# Power.net
KiCad netlist of a schematic drawn in Altium Designer
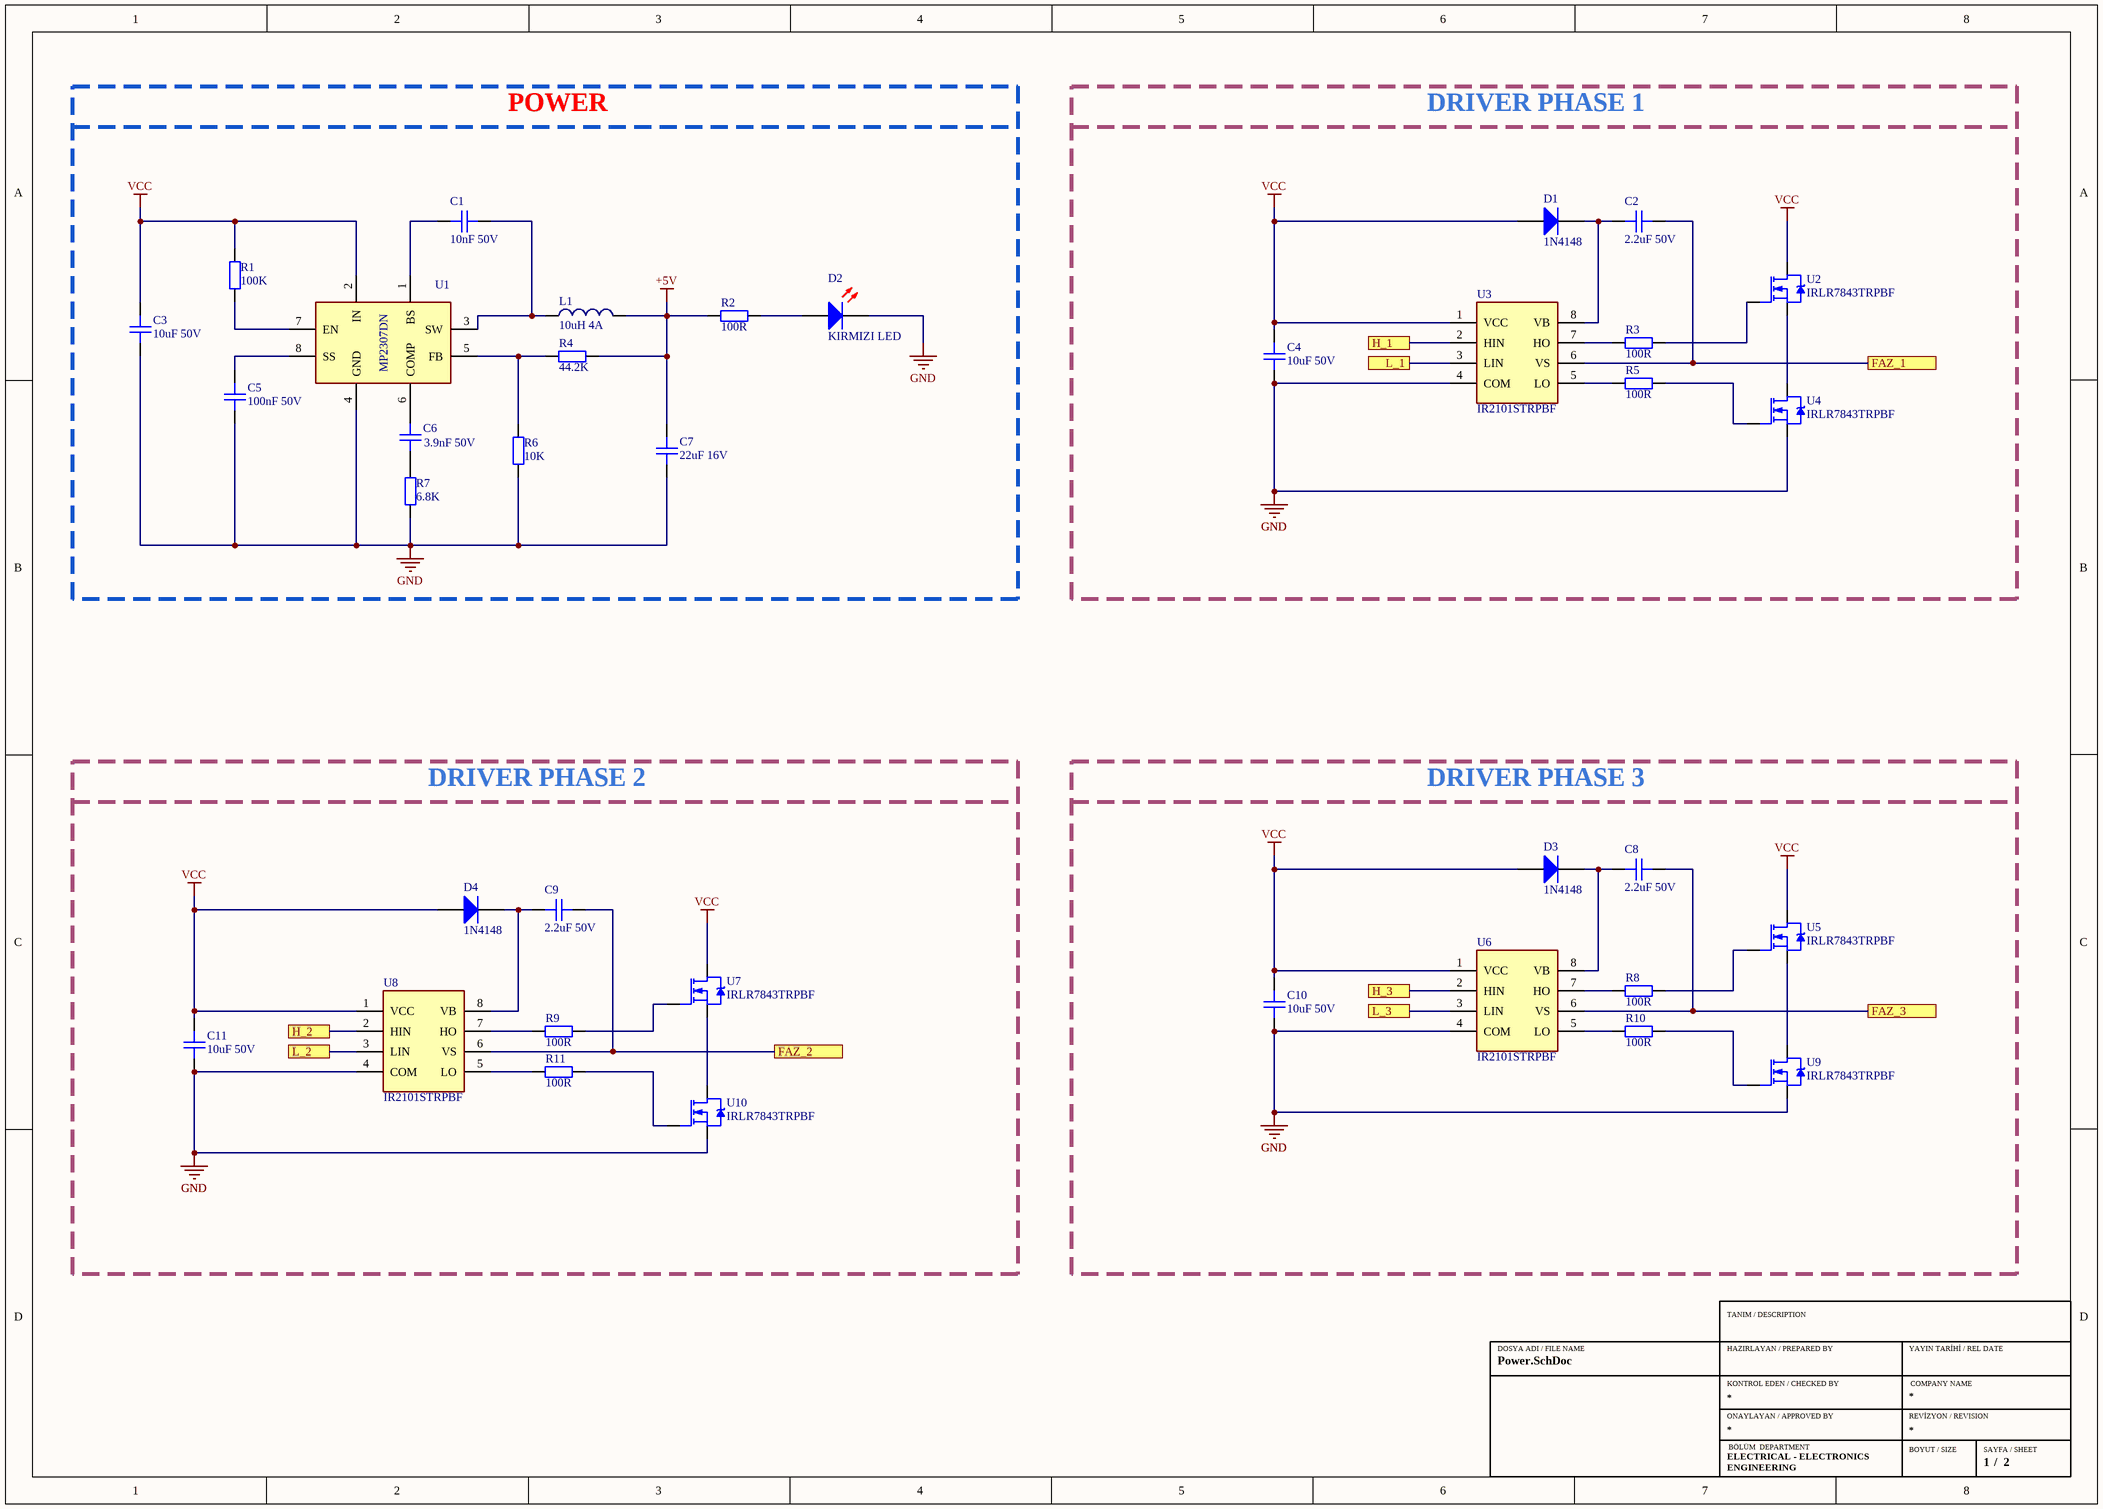
[diagram p0: Power.SchDoc]

(export (version "E")
  (design (tool "Eeschema 10.0.6"))
  (components
    (comp (ref "C1")
      (value "CAP CER 10000PF 50V X7R 0805")
      (footprint "CAP 0805/2012")
      (description "10000pF ±10% 50V Ceramic Capacitor X7R 0805 (2012 Metric)")
      (fields (field (name "DEGER") "10nF 50V"))
      (libsource (lib "PROJE") (part "10nF 50V 0805"))
    )
    (comp (ref "C2")
      (value "CAP CER 2.2UF 50V X5R 1206")
      (footprint "CAP 1206/3216")
      (description "2.2µF ±10% 50V Ceramic Capacitor X5R 1206 (3216 Metric)")
      (fields (field (name "DEGER") "2.2uF 50V"))
      (libsource (lib "PROJE") (part "2.2uF 50V 1206"))
    )
    (comp (ref "C3")
      (value "CAP CER 10UF 50V X5R 1206")
      (footprint "CAP 1206/3216")
      (description "10µF ±10% 50V Ceramic Capacitor X5R 1206 (3216 Metric)")
      (fields (field (name "DEGER") "10uF 50V"))
      (libsource (lib "PROJE") (part "10uF 50V 1206"))
    )
    (comp (ref "C4")
      (value "CAP CER 10UF 50V X5R 1206")
      (footprint "CAP 1206/3216")
      (description "10µF ±10% 50V Ceramic Capacitor X5R 1206 (3216 Metric)")
      (fields (field (name "DEGER") "10uF 50V"))
      (libsource (lib "PROJE") (part "10uF 50V 1206"))
    )
    (comp (ref "C5")
      (value "CAP CER 0.1UF 50V X7R 0805")
      (footprint "CAP 0805/2012")
      (description "0.1µF ±10% 50V Ceramic Capacitor X7R 0805 (2012 Metric)")
      (fields (field (name "DEGER") "100nF 50V"))
      (libsource (lib "PROJE") (part "100nF 50V 0805"))
    )
    (comp (ref "C6")
      (value "CAP CER 3900PF 50V X7R 0805")
      (footprint "CAP 0805/2012")
      (description "3900pF ±10% 50V Ceramic Capacitor X7R 0805 (2012 Metric)")
      (fields (field (name "DEGER") "3.9nF 50V"))
      (libsource (lib "PROJE") (part "3.9nF 50V 0805"))
    )
    (comp (ref "C7")
      (value "CAP CERAMIC 22UF 16V X7S 20% PAD")
      (footprint "CAP 1206/3216")
      (description "22µF ±20% 16V Ceramic Capacitor X7S 1206 (3216 Metric)")
      (fields (field (name "DEGER") "22uF 16V"))
      (libsource (lib "PROJE") (part "22uF 16V 1206"))
    )
    (comp (ref "C8")
      (value "CAP CER 2.2UF 50V X5R 1206")
      (footprint "CAP 1206/3216")
      (description "2.2µF ±10% 50V Ceramic Capacitor X5R 1206 (3216 Metric)")
      (fields (field (name "DEGER") "2.2uF 50V"))
      (libsource (lib "PROJE") (part "2.2uF 50V 1206"))
    )
    (comp (ref "C9")
      (value "CAP CER 2.2UF 50V X5R 1206")
      (footprint "CAP 1206/3216")
      (description "2.2µF ±10% 50V Ceramic Capacitor X5R 1206 (3216 Metric)")
      (fields (field (name "DEGER") "2.2uF 50V"))
      (libsource (lib "PROJE") (part "2.2uF 50V 1206"))
    )
    (comp (ref "C10")
      (value "CAP CER 10UF 50V X5R 1206")
      (footprint "CAP 1206/3216")
      (description "10µF ±10% 50V Ceramic Capacitor X5R 1206 (3216 Metric)")
      (fields (field (name "DEGER") "10uF 50V"))
      (libsource (lib "PROJE") (part "10uF 50V 1206"))
    )
    (comp (ref "C11")
      (value "CAP CER 10UF 50V X5R 1206")
      (footprint "CAP 1206/3216")
      (description "10µF ±10% 50V Ceramic Capacitor X5R 1206 (3216 Metric)")
      (fields (field (name "DEGER") "10uF 50V"))
      (libsource (lib "PROJE") (part "10uF 50V 1206"))
    )
    (comp (ref "D1")
      (value "1N4148 Diyot")
      (footprint "SOD-123")
      (description "DIODE GEN PURP 100V 150MA SOD123")
      (fields (field (name "DEGER") "1N4148"))
      (libsource (lib "PROJE") (part "1N4148"))
    )
    (comp (ref "D2")
      (value "Red 645nm LED Indication - Discrete 1.8V 0805")
      (footprint "SMD: LED 0805/2012 RED")
      (description "LED RED DIFFUSED 0805 SMD")
      (fields (field (name "DEGER") "KIRMIZI LED"))
      (libsource (lib "PROJE") (part "LED_Kırmızı"))
    )
    (comp (ref "D3")
      (value "1N4148 Diyot")
      (footprint "SOD-123")
      (description "DIODE GEN PURP 100V 150MA SOD123")
      (fields (field (name "DEGER") "1N4148"))
      (libsource (lib "PROJE") (part "1N4148"))
    )
    (comp (ref "D4")
      (value "1N4148 Diyot")
      (footprint "SOD-123")
      (description "DIODE GEN PURP 100V 150MA SOD123")
      (fields (field (name "DEGER") "1N4148"))
      (libsource (lib "PROJE") (part "1N4148"))
    )
    (comp (ref "L1")
      (value "FIXED IND 10UH 4A 68 MOHM SMD")
      (footprint "ASPI-0630LR-100M-T15")
      (description "10µH Shielded Molded Inductor 4A 68mOhm Max Nonstandard")
      (fields (field (name "DEGER") "10uH 4A"))
      (libsource (lib "PROJE") (part "10uH 4A"))
    )
    (comp (ref "R1")
      (value "RES SMD 100K OHM 1% 1/8W 0805")
      (footprint "RES_0805")
      (description "100 kOhms ±1% 0.125W, 1/8W Chip Resistor 0805 (2012 Metric) Moisture Resistant Thick Film")
      (fields (field (name "DEGER") "100K"))
      (libsource (lib "PROJE") (part "100K 0805"))
    )
    (comp (ref "R2")
      (value "RES SMD 100 OHM 1% 1/8W 0805")
      (footprint "RES_0805")
      (description "100 Ohms ±1% 0.125W, 1/8W Chip Resistor 0805 (2012 Metric) Moisture Resistant Thick Film")
      (fields (field (name "DEGER") "100R"))
      (libsource (lib "PROJE") (part "100R 0805"))
    )
    (comp (ref "R3")
      (value "RES SMD 100 OHM 1% 1/8W 0805")
      (footprint "RES_0805")
      (description "100 Ohms ±1% 0.125W, 1/8W Chip Resistor 0805 (2012 Metric) Moisture Resistant Thick Film")
      (fields (field (name "DEGER") "100R"))
      (libsource (lib "PROJE") (part "100R 0805"))
    )
    (comp (ref "R4")
      (value "RES SMD 44.2K OHM 1% 1/8W 0805")
      (footprint "RES_0805")
      (description "44.2 kOhms ±1% 0.125W, 1/8W Chip Resistor 0805 (2012 Metric) Moisture Resistant Thick Film")
      (fields (field (name "DEGER") "44.2K"))
      (libsource (lib "PROJE") (part "44.2K 0805"))
    )
    (comp (ref "R5")
      (value "RES SMD 100 OHM 1% 1/8W 0805")
      (footprint "RES_0805")
      (description "100 Ohms ±1% 0.125W, 1/8W Chip Resistor 0805 (2012 Metric) Moisture Resistant Thick Film")
      (fields (field (name "DEGER") "100R"))
      (libsource (lib "PROJE") (part "100R 0805"))
    )
    (comp (ref "R6")
      (value "RES SMD 10K OHM 1% 1/8W 0805")
      (footprint "RES_0805")
      (description "10 kOhms ±1% 0.125W, 1/8W Chip Resistor 0805 (2012 Metric) Moisture Resistant Thick Film")
      (fields (field (name "DEGER") "10K"))
      (libsource (lib "PROJE") (part "10K 0805"))
    )
    (comp (ref "R7")
      (value "RES SMD 6.8K OHM 1% 1/8W 0805")
      (footprint "RES_0805")
      (description "6.8 kOhms ±1% 0.125W, 1/8W Chip Resistor 0805 (2012 Metric) Moisture Resistant Thick Film")
      (fields (field (name "DEGER") "6.8K"))
      (libsource (lib "PROJE") (part "6.8K 0805"))
    )
    (comp (ref "R8")
      (value "RES SMD 100 OHM 1% 1/8W 0805")
      (footprint "RES_0805")
      (description "100 Ohms ±1% 0.125W, 1/8W Chip Resistor 0805 (2012 Metric) Moisture Resistant Thick Film")
      (fields (field (name "DEGER") "100R"))
      (libsource (lib "PROJE") (part "100R 0805"))
    )
    (comp (ref "R9")
      (value "RES SMD 100 OHM 1% 1/8W 0805")
      (footprint "RES_0805")
      (description "100 Ohms ±1% 0.125W, 1/8W Chip Resistor 0805 (2012 Metric) Moisture Resistant Thick Film")
      (fields (field (name "DEGER") "100R"))
      (libsource (lib "PROJE") (part "100R 0805"))
    )
    (comp (ref "R10")
      (value "RES SMD 100 OHM 1% 1/8W 0805")
      (footprint "RES_0805")
      (description "100 Ohms ±1% 0.125W, 1/8W Chip Resistor 0805 (2012 Metric) Moisture Resistant Thick Film")
      (fields (field (name "DEGER") "100R"))
      (libsource (lib "PROJE") (part "100R 0805"))
    )
    (comp (ref "R11")
      (value "RES SMD 100 OHM 1% 1/8W 0805")
      (footprint "RES_0805")
      (description "100 Ohms ±1% 0.125W, 1/8W Chip Resistor 0805 (2012 Metric) Moisture Resistant Thick Film")
      (fields (field (name "DEGER") "100R"))
      (libsource (lib "PROJE") (part "100R 0805"))
    )
    (comp (ref "U1")
      (value "IC REG BUCK ADJUSTABLE 3A 8SOIC")
      (footprint "SOIC8_PAD")
      (fields (field (name "DEGER") "MP2307DN"))
      (libsource (lib "PROJE") (part "MP2307DN"))
    )
    (comp (ref "U2")
      (value "MOSFET N-CH 30V 161A DPAK")
      (footprint "DPAK")
      (description "N-Channel 30V 161A (Tc) 140W (Tc) Surface Mount D-Pak")
      (fields (field (name "DEGER") "IRLR7843TRPBF"))
      (libsource (lib "PROJE") (part "IRLR7843"))
    )
    (comp (ref "U3")
      (value "IC GATE DRVR HALF-BRIDGE 8SOIC")
      (footprint "SOIC8")
      (description "Half-Bridge Gate Driver IC Non-Inverting 8-SOIC")
      (fields (field (name "DEGER") "IR2101STRPBF"))
      (libsource (lib "PROJE") (part "IR2101"))
    )
    (comp (ref "U4")
      (value "MOSFET N-CH 30V 161A DPAK")
      (footprint "DPAK")
      (description "N-Channel 30V 161A (Tc) 140W (Tc) Surface Mount D-Pak")
      (fields (field (name "DEGER") "IRLR7843TRPBF"))
      (libsource (lib "PROJE") (part "IRLR7843"))
    )
    (comp (ref "U5")
      (value "MOSFET N-CH 30V 161A DPAK")
      (footprint "DPAK")
      (description "N-Channel 30V 161A (Tc) 140W (Tc) Surface Mount D-Pak")
      (fields (field (name "DEGER") "IRLR7843TRPBF"))
      (libsource (lib "PROJE") (part "IRLR7843"))
    )
    (comp (ref "U6")
      (value "IC GATE DRVR HALF-BRIDGE 8SOIC")
      (footprint "SOIC8")
      (description "Half-Bridge Gate Driver IC Non-Inverting 8-SOIC")
      (fields (field (name "DEGER") "IR2101STRPBF"))
      (libsource (lib "PROJE") (part "IR2101"))
    )
    (comp (ref "U7")
      (value "MOSFET N-CH 30V 161A DPAK")
      (footprint "DPAK")
      (description "N-Channel 30V 161A (Tc) 140W (Tc) Surface Mount D-Pak")
      (fields (field (name "DEGER") "IRLR7843TRPBF"))
      (libsource (lib "PROJE") (part "IRLR7843"))
    )
    (comp (ref "U8")
      (value "IC GATE DRVR HALF-BRIDGE 8SOIC")
      (footprint "SOIC8")
      (description "Half-Bridge Gate Driver IC Non-Inverting 8-SOIC")
      (fields (field (name "DEGER") "IR2101STRPBF"))
      (libsource (lib "PROJE") (part "IR2101"))
    )
    (comp (ref "U9")
      (value "MOSFET N-CH 30V 161A DPAK")
      (footprint "DPAK")
      (description "N-Channel 30V 161A (Tc) 140W (Tc) Surface Mount D-Pak")
      (fields (field (name "DEGER") "IRLR7843TRPBF"))
      (libsource (lib "PROJE") (part "IRLR7843"))
    )
    (comp (ref "U10")
      (value "MOSFET N-CH 30V 161A DPAK")
      (footprint "DPAK")
      (description "N-Channel 30V 161A (Tc) 140W (Tc) Surface Mount D-Pak")
      (fields (field (name "DEGER") "IRLR7843TRPBF"))
      (libsource (lib "PROJE") (part "IRLR7843"))
    )
  )
  (nets
    (net (code "1") (name "+5V") (class "Default")
      (node (ref "C7") (pin "2") (pinfunction "2_2") (pintype "passive"))
      (node (ref "L1") (pin "2") (pinfunction "2_2") (pintype "passive"))
      (node (ref "R2") (pin "1") (pinfunction "1_1") (pintype "passive"))
      (node (ref "R4") (pin "2") (pinfunction "2_2") (pintype "passive"))
    )
    (net (code "2") (name "/FAZ_1") (class "Default")
      (node (ref "C2") (pin "2") (pinfunction "2_2") (pintype "passive"))
      (node (ref "U3") (pin "6") (pinfunction "VS_6") (pintype "passive"))
    )
    (net (code "3") (name "/FAZ_2") (class "Default")
      (node (ref "C9") (pin "2") (pinfunction "2_2") (pintype "passive"))
      (node (ref "U8") (pin "6") (pinfunction "VS_6") (pintype "passive"))
    )
    (net (code "4") (name "/FAZ_3") (class "Default")
      (node (ref "C8") (pin "2") (pinfunction "2_2") (pintype "passive"))
      (node (ref "U6") (pin "6") (pinfunction "VS_6") (pintype "passive"))
    )
    (net (code "5") (name "/H_1") (class "Default")
      (node (ref "U3") (pin "2") (pinfunction "HIN_2") (pintype "passive"))
    )
    (net (code "6") (name "/H_2") (class "Default")
      (node (ref "U8") (pin "2") (pinfunction "HIN_2") (pintype "passive"))
    )
    (net (code "7") (name "/H_3") (class "Default")
      (node (ref "U6") (pin "2") (pinfunction "HIN_2") (pintype "passive"))
    )
    (net (code "8") (name "/L_1") (class "Default")
      (node (ref "U3") (pin "3") (pinfunction "LIN_3") (pintype "passive"))
    )
    (net (code "9") (name "/L_2") (class "Default")
      (node (ref "U8") (pin "3") (pinfunction "LIN_3") (pintype "passive"))
    )
    (net (code "10") (name "/L_3") (class "Default")
      (node (ref "U6") (pin "3") (pinfunction "LIN_3") (pintype "passive"))
    )
    (net (code "11") (name "GND") (class "Default")
      (node (ref "C10") (pin "1") (pinfunction "1_1") (pintype "passive"))
      (node (ref "C11") (pin "1") (pinfunction "1_1") (pintype "passive"))
      (node (ref "C3") (pin "1") (pinfunction "1_1") (pintype "passive"))
      (node (ref "C4") (pin "1") (pinfunction "1_1") (pintype "passive"))
      (node (ref "C5") (pin "1") (pinfunction "1_1") (pintype "passive"))
      (node (ref "C7") (pin "1") (pinfunction "1_1") (pintype "passive"))
      (node (ref "D2") (pin "2") (pinfunction "K_2") (pintype "passive"))
      (node (ref "R6") (pin "1") (pinfunction "1_1") (pintype "passive"))
      (node (ref "R7") (pin "1") (pinfunction "1_1") (pintype "passive"))
      (node (ref "U1") (pin "4") (pinfunction "GND_4") (pintype "passive"))
      (node (ref "U10") (pin "3") (pinfunction "S_3") (pintype "passive"))
      (node (ref "U3") (pin "4") (pinfunction "COM_4") (pintype "passive"))
      (node (ref "U4") (pin "3") (pinfunction "S_3") (pintype "passive"))
      (node (ref "U6") (pin "4") (pinfunction "COM_4") (pintype "passive"))
      (node (ref "U8") (pin "4") (pinfunction "COM_4") (pintype "passive"))
      (node (ref "U9") (pin "3") (pinfunction "S_3") (pintype "passive"))
    )
    (net (code "12") (name "Net-(C6-Pad1)") (class "Default")
      (node (ref "C6") (pin "1") (pinfunction "1_1") (pintype "passive"))
      (node (ref "R7") (pin "2") (pinfunction "2_2") (pintype "passive"))
    )
    (net (code "13") (name "Net-(D1-K)") (class "Default")
      (node (ref "C2") (pin "1") (pinfunction "1_1") (pintype "passive"))
      (node (ref "D1") (pin "2") (pinfunction "K_2") (pintype "passive"))
      (node (ref "U3") (pin "8") (pinfunction "VB_8") (pintype "passive"))
    )
    (net (code "14") (name "Net-(D2-A)") (class "Default")
      (node (ref "D2") (pin "1") (pinfunction "A_1") (pintype "passive"))
      (node (ref "R2") (pin "2") (pinfunction "2_2") (pintype "passive"))
    )
    (net (code "15") (name "Net-(D3-K)") (class "Default")
      (node (ref "C8") (pin "1") (pinfunction "1_1") (pintype "passive"))
      (node (ref "D3") (pin "2") (pinfunction "K_2") (pintype "passive"))
      (node (ref "U6") (pin "8") (pinfunction "VB_8") (pintype "passive"))
    )
    (net (code "16") (name "Net-(D4-K)") (class "Default")
      (node (ref "C9") (pin "1") (pinfunction "1_1") (pintype "passive"))
      (node (ref "D4") (pin "2") (pinfunction "K_2") (pintype "passive"))
      (node (ref "U8") (pin "8") (pinfunction "VB_8") (pintype "passive"))
    )
    (net (code "17") (name "Net-(U1-BS)") (class "Default")
      (node (ref "C1") (pin "1") (pinfunction "1_1") (pintype "passive"))
      (node (ref "U1") (pin "1") (pinfunction "BS_1") (pintype "passive"))
    )
    (net (code "18") (name "Net-(U1-COMP)") (class "Default")
      (node (ref "C6") (pin "2") (pinfunction "2_2") (pintype "passive"))
      (node (ref "U1") (pin "6") (pinfunction "COMP_6") (pintype "passive"))
    )
    (net (code "19") (name "Net-(U1-EN)") (class "Default")
      (node (ref "R1") (pin "1") (pinfunction "1_1") (pintype "passive"))
      (node (ref "U1") (pin "7") (pinfunction "EN_7") (pintype "passive"))
    )
    (net (code "20") (name "Net-(U1-FB)") (class "Default")
      (node (ref "R4") (pin "1") (pinfunction "1_1") (pintype "passive"))
      (node (ref "R6") (pin "2") (pinfunction "2_2") (pintype "passive"))
      (node (ref "U1") (pin "5") (pinfunction "FB_5") (pintype "passive"))
    )
    (net (code "21") (name "Net-(U1-SS)") (class "Default")
      (node (ref "C5") (pin "2") (pinfunction "2_2") (pintype "passive"))
      (node (ref "U1") (pin "8") (pinfunction "SS_8") (pintype "passive"))
    )
    (net (code "22") (name "Net-(U1-SW)") (class "Default")
      (node (ref "C1") (pin "2") (pinfunction "2_2") (pintype "passive"))
      (node (ref "L1") (pin "1") (pinfunction "1_1") (pintype "passive"))
      (node (ref "U1") (pin "3") (pinfunction "SW_3") (pintype "passive"))
    )
    (net (code "23") (name "Net-(U2-G)") (class "Default")
      (node (ref "R3") (pin "2") (pinfunction "2_2") (pintype "passive"))
      (node (ref "U2") (pin "1") (pinfunction "G_1") (pintype "passive"))
    )
    (net (code "24") (name "Net-(U2-S)") (class "Default")
      (node (ref "U2") (pin "3") (pinfunction "S_3") (pintype "passive"))
      (node (ref "U4") (pin "4") (pinfunction "D_4") (pintype "passive"))
    )
    (net (code "25") (name "Net-(U3-HO)") (class "Default")
      (node (ref "R3") (pin "1") (pinfunction "1_1") (pintype "passive"))
      (node (ref "U3") (pin "7") (pinfunction "HO_7") (pintype "passive"))
    )
    (net (code "26") (name "Net-(U3-LO)") (class "Default")
      (node (ref "R5") (pin "1") (pinfunction "1_1") (pintype "passive"))
      (node (ref "U3") (pin "5") (pinfunction "LO_5") (pintype "passive"))
    )
    (net (code "27") (name "Net-(U4-G)") (class "Default")
      (node (ref "R5") (pin "2") (pinfunction "2_2") (pintype "passive"))
      (node (ref "U4") (pin "1") (pinfunction "G_1") (pintype "passive"))
    )
    (net (code "28") (name "Net-(U5-G)") (class "Default")
      (node (ref "R8") (pin "2") (pinfunction "2_2") (pintype "passive"))
      (node (ref "U5") (pin "1") (pinfunction "G_1") (pintype "passive"))
    )
    (net (code "29") (name "Net-(U5-S)") (class "Default")
      (node (ref "U5") (pin "3") (pinfunction "S_3") (pintype "passive"))
      (node (ref "U9") (pin "4") (pinfunction "D_4") (pintype "passive"))
    )
    (net (code "30") (name "Net-(U6-HO)") (class "Default")
      (node (ref "R8") (pin "1") (pinfunction "1_1") (pintype "passive"))
      (node (ref "U6") (pin "7") (pinfunction "HO_7") (pintype "passive"))
    )
    (net (code "31") (name "Net-(U6-LO)") (class "Default")
      (node (ref "R10") (pin "1") (pinfunction "1_1") (pintype "passive"))
      (node (ref "U6") (pin "5") (pinfunction "LO_5") (pintype "passive"))
    )
    (net (code "32") (name "Net-(U7-G)") (class "Default")
      (node (ref "R9") (pin "2") (pinfunction "2_2") (pintype "passive"))
      (node (ref "U7") (pin "1") (pinfunction "G_1") (pintype "passive"))
    )
    (net (code "33") (name "Net-(U8-HO)") (class "Default")
      (node (ref "R9") (pin "1") (pinfunction "1_1") (pintype "passive"))
      (node (ref "U8") (pin "7") (pinfunction "HO_7") (pintype "passive"))
    )
    (net (code "34") (name "Net-(U8-LO)") (class "Default")
      (node (ref "R11") (pin "1") (pinfunction "1_1") (pintype "passive"))
      (node (ref "U8") (pin "5") (pinfunction "LO_5") (pintype "passive"))
    )
    (net (code "35") (name "Net-(U9-G)") (class "Default")
      (node (ref "R10") (pin "2") (pinfunction "2_2") (pintype "passive"))
      (node (ref "U9") (pin "1") (pinfunction "G_1") (pintype "passive"))
    )
    (net (code "36") (name "Net-(U10-D)") (class "Default")
      (node (ref "U10") (pin "4") (pinfunction "D_4") (pintype "passive"))
      (node (ref "U7") (pin "3") (pinfunction "S_3") (pintype "passive"))
    )
    (net (code "37") (name "Net-(U10-G)") (class "Default")
      (node (ref "R11") (pin "2") (pinfunction "2_2") (pintype "passive"))
      (node (ref "U10") (pin "1") (pinfunction "G_1") (pintype "passive"))
    )
    (net (code "38") (name "VCC") (class "Default")
      (node (ref "C10") (pin "2") (pinfunction "2_2") (pintype "passive"))
      (node (ref "C11") (pin "2") (pinfunction "2_2") (pintype "passive"))
      (node (ref "C3") (pin "2") (pinfunction "2_2") (pintype "passive"))
      (node (ref "C4") (pin "2") (pinfunction "2_2") (pintype "passive"))
      (node (ref "D1") (pin "1") (pinfunction "A_1") (pintype "passive"))
      (node (ref "D3") (pin "1") (pinfunction "A_1") (pintype "passive"))
      (node (ref "D4") (pin "1") (pinfunction "A_1") (pintype "passive"))
      (node (ref "R1") (pin "2") (pinfunction "2_2") (pintype "passive"))
      (node (ref "U1") (pin "2") (pinfunction "IN_2") (pintype "passive"))
      (node (ref "U2") (pin "4") (pinfunction "D_4") (pintype "passive"))
      (node (ref "U3") (pin "1") (pinfunction "VCC_1") (pintype "passive"))
      (node (ref "U5") (pin "4") (pinfunction "D_4") (pintype "passive"))
      (node (ref "U6") (pin "1") (pinfunction "VCC_1") (pintype "passive"))
      (node (ref "U7") (pin "4") (pinfunction "D_4") (pintype "passive"))
      (node (ref "U8") (pin "1") (pinfunction "VCC_1") (pintype "passive"))
    )
  )
)
